# 4gewinnt_01.net
KiCad netlist of a schematic drawn in EAGLE
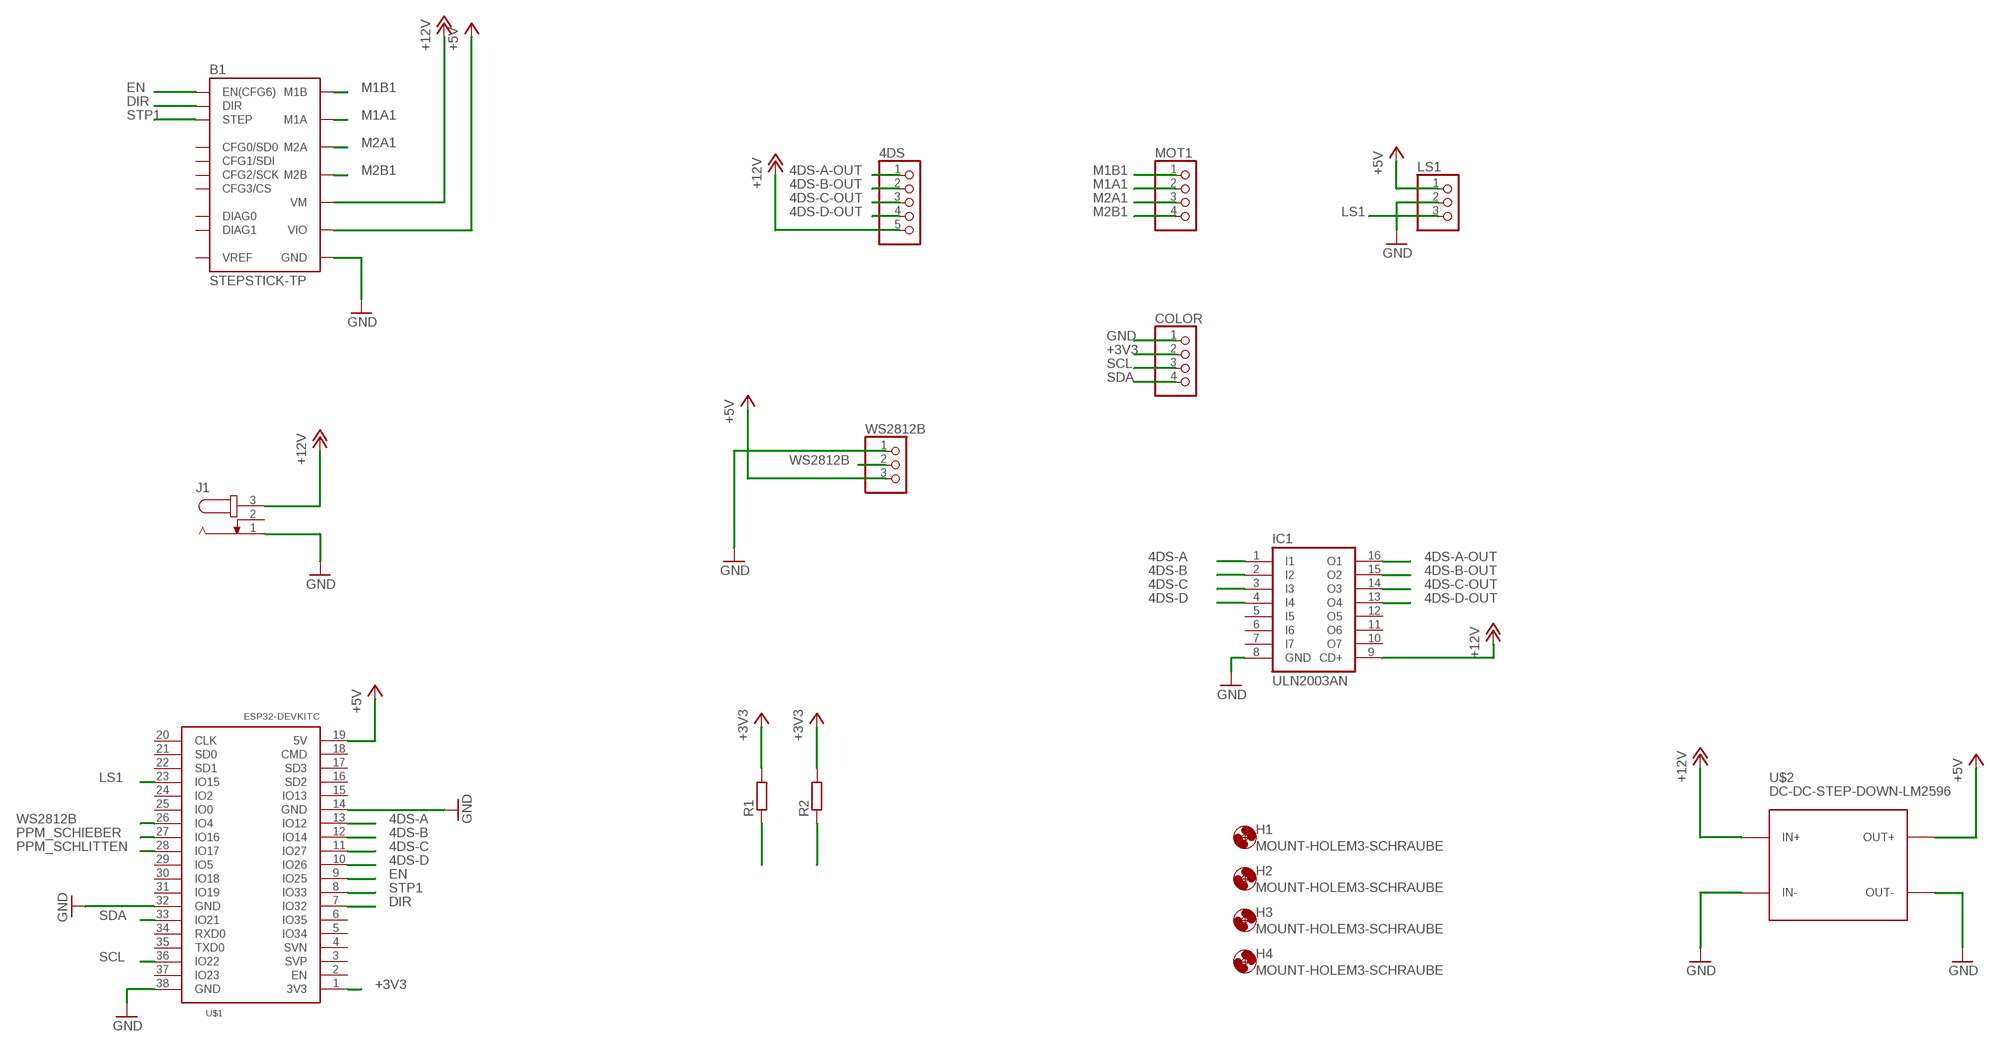
[diagram p0: schematic, sheet 1]

(export (version "E")
  (design (tool "Eeschema 10.0.6"))
  (components
    (comp (ref "4DS")
      (value "PINHD-1X5")
      (footprint "eagle-import:1X05")
      (libsource (lib "eagle-import") (part "PINHD-1X5"))
    )
    (comp (ref "B1")
      (value "STEPSTICK-TP")
      (footprint "eagle-import:STEPSTICK_TP")
      (libsource (lib "eagle-import") (part "STEPSTICK-TP"))
    )
    (comp (ref "COLOR")
      (value "PINHD-1X4")
      (footprint "eagle-import:1X04")
      (libsource (lib "eagle-import") (part "PINHD-1X4"))
    )
    (comp (ref "H1")
      (value "MOUNT-HOLEM3-SCHRAUBE")
      (footprint "eagle-import:M3-SCHRAUBE")
      (libsource (lib "eagle-import") (part "MOUNT-HOLEM3-SCHRAUBE"))
    )
    (comp (ref "H2")
      (value "MOUNT-HOLEM3-SCHRAUBE")
      (footprint "eagle-import:M3-SCHRAUBE")
      (libsource (lib "eagle-import") (part "MOUNT-HOLEM3-SCHRAUBE"))
    )
    (comp (ref "H3")
      (value "MOUNT-HOLEM3-SCHRAUBE")
      (footprint "eagle-import:M3-SCHRAUBE")
      (libsource (lib "eagle-import") (part "MOUNT-HOLEM3-SCHRAUBE"))
    )
    (comp (ref "H4")
      (value "MOUNT-HOLEM3-SCHRAUBE")
      (footprint "eagle-import:M3-SCHRAUBE")
      (libsource (lib "eagle-import") (part "MOUNT-HOLEM3-SCHRAUBE"))
    )
    (comp (ref "IC1")
      (value "ULN2003AN")
      (footprint "eagle-import:DIL16")
      (libsource (lib "eagle-import") (part "ULN2003AN"))
    )
    (comp (ref "J1")
      (value "JACK-PLUG2")
      (footprint "eagle-import:DC5.5-2.5")
      (libsource (lib "eagle-import") (part "JACK-PLUG2"))
    )
    (comp (ref "LS1")
      (value "PINHD-1X3")
      (footprint "eagle-import:1X03")
      (libsource (lib "eagle-import") (part "PINHD-1X3"))
    )
    (comp (ref "MOT1")
      (value "PINHD-1X4")
      (footprint "eagle-import:1X04")
      (libsource (lib "eagle-import") (part "PINHD-1X4"))
    )
    (comp (ref "R1")
      (value "R-EU_0207/15")
      (footprint "eagle-import:0207_15")
      (libsource (lib "eagle-import") (part "R-EU_0207/15"))
    )
    (comp (ref "R2")
      (value "R-EU_0207/15")
      (footprint "eagle-import:0207_15")
      (libsource (lib "eagle-import") (part "R-EU_0207/15"))
    )
    (comp (ref "U$1")
      (value "ESP32DEVKITCAZDELIVERY-ESP32")
      (footprint "eagle-import:AZDELIVERY-ESP32")
      (libsource (lib "eagle-import") (part "ESP32DEVKITCAZDELIVERY-ESP32"))
    )
    (comp (ref "U$2")
      (value "DC-DC-STEP-DOWN-LM2596")
      (footprint "eagle-import:DC-DC-STEP-DOWN-LM2596")
      (libsource (lib "eagle-import") (part "DC-DC-STEP-DOWN-LM2596"))
    )
    (comp (ref "WS2812B")
      (value "PINHD-1X3")
      (footprint "eagle-import:1X03")
      (libsource (lib "eagle-import") (part "PINHD-1X3"))
    )
  )
  (nets
    (net (code "1") (name "+3V3") (class "Default")
      (node (ref "COLOR") (pin "2") (pinfunction "2_2") (pintype "passive"))
      (node (ref "R1") (pin "2") (pinfunction "2_2") (pintype "passive"))
      (node (ref "R2") (pin "2") (pinfunction "2_2") (pintype "passive"))
      (node (ref "U$1") (pin "1") (pinfunction "3V3_1") (pintype "bidirectional"))
    )
    (net (code "2") (name "+5V") (class "Default")
      (node (ref "B1") (pin "VIO") (pinfunction "VIO_VIO") (pintype "power_in"))
      (node (ref "LS1") (pin "1") (pinfunction "1_1") (pintype "passive"))
      (node (ref "U$1") (pin "19") (pinfunction "5V_19") (pintype "bidirectional"))
      (node (ref "U$2") (pin "OUT+") (pinfunction "OUT+_OUT+") (pintype "bidirectional"))
      (node (ref "WS2812B") (pin "3") (pinfunction "3_3") (pintype "passive"))
    )
    (net (code "3") (name "+12V") (class "Default")
      (node (ref "4DS") (pin "5") (pinfunction "5_5") (pintype "passive"))
      (node (ref "B1") (pin "VM") (pinfunction "VM_VM") (pintype "power_in"))
      (node (ref "IC1") (pin "9") (pinfunction "CD+_9") (pintype "passive"))
      (node (ref "J1") (pin "3") (pinfunction "3_3") (pintype "passive"))
      (node (ref "U$2") (pin "IN+") (pinfunction "IN+_IN+") (pintype "bidirectional"))
    )
    (net (code "4") (name "/4DS-A") (class "Default")
      (node (ref "IC1") (pin "1") (pinfunction "I1_1") (pintype "input"))
      (node (ref "U$1") (pin "13") (pinfunction "IO12_13") (pintype "bidirectional"))
    )
    (net (code "5") (name "/4DS-A-OUT") (class "Default")
      (node (ref "4DS") (pin "1") (pinfunction "1_1") (pintype "passive"))
      (node (ref "IC1") (pin "16") (pinfunction "O1_16") (pintype "open_collector"))
    )
    (net (code "6") (name "/4DS-B") (class "Default")
      (node (ref "IC1") (pin "2") (pinfunction "I2_2") (pintype "input"))
      (node (ref "U$1") (pin "12") (pinfunction "IO14_12") (pintype "bidirectional"))
    )
    (net (code "7") (name "/4DS-B-OUT") (class "Default")
      (node (ref "4DS") (pin "2") (pinfunction "2_2") (pintype "passive"))
      (node (ref "IC1") (pin "15") (pinfunction "O2_15") (pintype "open_collector"))
    )
    (net (code "8") (name "/4DS-C") (class "Default")
      (node (ref "IC1") (pin "3") (pinfunction "I3_3") (pintype "input"))
      (node (ref "U$1") (pin "11") (pinfunction "IO27_11") (pintype "bidirectional"))
    )
    (net (code "9") (name "/4DS-C-OUT") (class "Default")
      (node (ref "4DS") (pin "3") (pinfunction "3_3") (pintype "passive"))
      (node (ref "IC1") (pin "14") (pinfunction "O3_14") (pintype "open_collector"))
    )
    (net (code "10") (name "/4DS-D") (class "Default")
      (node (ref "IC1") (pin "4") (pinfunction "I4_4") (pintype "input"))
      (node (ref "U$1") (pin "10") (pinfunction "IO26_10") (pintype "bidirectional"))
    )
    (net (code "11") (name "/4DS-D-OUT") (class "Default")
      (node (ref "4DS") (pin "4") (pinfunction "4_4") (pintype "passive"))
      (node (ref "IC1") (pin "13") (pinfunction "O4_13") (pintype "open_collector"))
    )
    (net (code "12") (name "/DIR") (class "Default")
      (node (ref "B1") (pin "DIR") (pinfunction "DIR_DIR") (pintype "bidirectional"))
      (node (ref "U$1") (pin "7") (pinfunction "IO32_7") (pintype "bidirectional"))
    )
    (net (code "13") (name "/EN") (class "Default")
      (node (ref "B1") (pin "EN") (pinfunction "EN(CFG6)_EN") (pintype "bidirectional"))
      (node (ref "U$1") (pin "9") (pinfunction "IO25_9") (pintype "bidirectional"))
    )
    (net (code "14") (name "/LS1") (class "Default")
      (node (ref "LS1") (pin "3") (pinfunction "3_3") (pintype "passive"))
      (node (ref "U$1") (pin "23") (pinfunction "IO15_23") (pintype "bidirectional"))
    )
    (net (code "15") (name "/M1A1") (class "Default")
      (node (ref "B1") (pin "M1A") (pinfunction "M1A_M1A") (pintype "output"))
      (node (ref "MOT1") (pin "2") (pinfunction "2_2") (pintype "passive"))
    )
    (net (code "16") (name "/M1B1") (class "Default")
      (node (ref "B1") (pin "M1B") (pinfunction "M1B_M1B") (pintype "output"))
      (node (ref "MOT1") (pin "1") (pinfunction "1_1") (pintype "passive"))
    )
    (net (code "17") (name "/M2A1") (class "Default")
      (node (ref "B1") (pin "M2A") (pinfunction "M2A_M2A") (pintype "output"))
      (node (ref "MOT1") (pin "3") (pinfunction "3_3") (pintype "passive"))
    )
    (net (code "18") (name "/M2B1") (class "Default")
      (node (ref "B1") (pin "M2B") (pinfunction "M2B_M2B") (pintype "output"))
      (node (ref "MOT1") (pin "4") (pinfunction "4_4") (pintype "passive"))
    )
    (net (code "19") (name "/PPM_SCHIEBER") (class "Default")
      (node (ref "R1") (pin "1") (pinfunction "1_1") (pintype "passive"))
      (node (ref "U$1") (pin "27") (pinfunction "IO16_27") (pintype "bidirectional"))
    )
    (net (code "20") (name "/PPM_SCHLITTEN") (class "Default")
      (node (ref "R2") (pin "1") (pinfunction "1_1") (pintype "passive"))
      (node (ref "U$1") (pin "28") (pinfunction "IO17_28") (pintype "bidirectional"))
    )
    (net (code "21") (name "/SCL") (class "Default")
      (node (ref "COLOR") (pin "3") (pinfunction "3_3") (pintype "passive"))
      (node (ref "U$1") (pin "36") (pinfunction "IO22_36") (pintype "bidirectional"))
    )
    (net (code "22") (name "/SDA") (class "Default")
      (node (ref "COLOR") (pin "4") (pinfunction "4_4") (pintype "passive"))
      (node (ref "U$1") (pin "33") (pinfunction "IO21_33") (pintype "bidirectional"))
    )
    (net (code "23") (name "/STP1") (class "Default")
      (node (ref "B1") (pin "STEP") (pinfunction "STEP_STEP") (pintype "bidirectional"))
      (node (ref "U$1") (pin "8") (pinfunction "IO33_8") (pintype "bidirectional"))
    )
    (net (code "24") (name "/WS2812B") (class "Default")
      (node (ref "U$1") (pin "26") (pinfunction "IO4_26") (pintype "bidirectional"))
      (node (ref "WS2812B") (pin "2") (pinfunction "2_2") (pintype "passive"))
    )
    (net (code "25") (name "GND") (class "Default")
      (node (ref "B1") (pin "GND@1") (pinfunction "GND_GND@1") (pintype "power_in"))
      (node (ref "B1") (pin "GND@2") (pinfunction "GND_GND@2") (pintype "power_in"))
      (node (ref "COLOR") (pin "1") (pinfunction "1_1") (pintype "passive"))
      (node (ref "IC1") (pin "8") (pinfunction "GND_8") (pintype "power_in"))
      (node (ref "J1") (pin "1") (pinfunction "1_1") (pintype "passive"))
      (node (ref "LS1") (pin "2") (pinfunction "2_2") (pintype "passive"))
      (node (ref "U$1") (pin "14") (pinfunction "GND_14") (pintype "bidirectional"))
      (node (ref "U$1") (pin "32") (pinfunction "GND_32") (pintype "bidirectional"))
      (node (ref "U$1") (pin "38") (pinfunction "GND_38") (pintype "bidirectional"))
      (node (ref "U$2") (pin "IN-") (pinfunction "IN-_IN-") (pintype "bidirectional"))
      (node (ref "U$2") (pin "OUT-") (pinfunction "OUT-_OUT-") (pintype "bidirectional"))
      (node (ref "WS2812B") (pin "1") (pinfunction "1_1") (pintype "passive"))
    )
    (net (code "26") (name "unconnected-(B1-CFG0{slash}SD0-PadNC{slash}CFG0)") (class "Default")
      (node (ref "B1") (pin "NC/CFG0") (pinfunction "CFG0/SD0_NC/CFG0") (pintype "bidirectional"))
    )
    (net (code "27") (name "unconnected-(B1-CFG1{slash}SDI-PadCFG1)") (class "Default")
      (node (ref "B1") (pin "CFG1") (pinfunction "CFG1/SDI_CFG1") (pintype "bidirectional"))
    )
    (net (code "28") (name "unconnected-(B1-CFG2{slash}SCK-PadCFG2)") (class "Default")
      (node (ref "B1") (pin "CFG2") (pinfunction "CFG2/SCK_CFG2") (pintype "bidirectional"))
    )
    (net (code "29") (name "unconnected-(B1-CFG3{slash}CS-PadCFG3)") (class "Default")
      (node (ref "B1") (pin "CFG3") (pinfunction "CFG3/CS_CFG3") (pintype "bidirectional"))
    )
    (net (code "30") (name "unconnected-(B1-PadDIAG0)") (class "Default")
      (node (ref "B1") (pin "DIAG0") (pinfunction "DIAG0_DIAG0") (pintype "bidirectional"))
    )
    (net (code "31") (name "unconnected-(B1-PadDIAG1)") (class "Default")
      (node (ref "B1") (pin "DIAG1") (pinfunction "DIAG1_DIAG1") (pintype "bidirectional"))
    )
    (net (code "32") (name "unconnected-(B1-PadVREF)") (class "Default")
      (node (ref "B1") (pin "VREF") (pinfunction "VREF_VREF") (pintype "passive"))
    )
    (net (code "33") (name "unconnected-(IC1-I5-Pad5)") (class "Default")
      (node (ref "IC1") (pin "5") (pinfunction "I5_5") (pintype "input"))
    )
    (net (code "34") (name "unconnected-(IC1-I6-Pad6)") (class "Default")
      (node (ref "IC1") (pin "6") (pinfunction "I6_6") (pintype "input"))
    )
    (net (code "35") (name "unconnected-(IC1-I7-Pad7)") (class "Default")
      (node (ref "IC1") (pin "7") (pinfunction "I7_7") (pintype "input"))
    )
    (net (code "36") (name "unconnected-(IC1-O5-Pad12)") (class "Default")
      (node (ref "IC1") (pin "12") (pinfunction "O5_12") (pintype "open_collector"))
    )
    (net (code "37") (name "unconnected-(IC1-O6-Pad11)") (class "Default")
      (node (ref "IC1") (pin "11") (pinfunction "O6_11") (pintype "open_collector"))
    )
    (net (code "38") (name "unconnected-(IC1-O7-Pad10)") (class "Default")
      (node (ref "IC1") (pin "10") (pinfunction "O7_10") (pintype "open_collector"))
    )
    (net (code "39") (name "unconnected-(J1-Pad2)") (class "Default")
      (node (ref "J1") (pin "2") (pinfunction "2_2") (pintype "passive"))
    )
    (net (code "40") (name "unconnected-(U$1-CLK-Pad20)") (class "Default")
      (node (ref "U$1") (pin "20") (pinfunction "CLK_20") (pintype "bidirectional"))
    )
    (net (code "41") (name "unconnected-(U$1-CMD-Pad18)") (class "Default")
      (node (ref "U$1") (pin "18") (pinfunction "CMD_18") (pintype "bidirectional"))
    )
    (net (code "42") (name "unconnected-(U$1-EN-Pad2)") (class "Default")
      (node (ref "U$1") (pin "2") (pinfunction "EN_2") (pintype "bidirectional"))
    )
    (net (code "43") (name "unconnected-(U$1-IO0-Pad25)") (class "Default")
      (node (ref "U$1") (pin "25") (pinfunction "IO0_25") (pintype "bidirectional"))
    )
    (net (code "44") (name "unconnected-(U$1-IO2-Pad24)") (class "Default")
      (node (ref "U$1") (pin "24") (pinfunction "IO2_24") (pintype "bidirectional"))
    )
    (net (code "45") (name "unconnected-(U$1-IO5-Pad29)") (class "Default")
      (node (ref "U$1") (pin "29") (pinfunction "IO5_29") (pintype "bidirectional"))
    )
    (net (code "46") (name "unconnected-(U$1-IO13-Pad15)") (class "Default")
      (node (ref "U$1") (pin "15") (pinfunction "IO13_15") (pintype "bidirectional"))
    )
    (net (code "47") (name "unconnected-(U$1-IO18-Pad30)") (class "Default")
      (node (ref "U$1") (pin "30") (pinfunction "IO18_30") (pintype "bidirectional"))
    )
    (net (code "48") (name "unconnected-(U$1-IO19-Pad31)") (class "Default")
      (node (ref "U$1") (pin "31") (pinfunction "IO19_31") (pintype "bidirectional"))
    )
    (net (code "49") (name "unconnected-(U$1-IO23-Pad37)") (class "Default")
      (node (ref "U$1") (pin "37") (pinfunction "IO23_37") (pintype "bidirectional"))
    )
    (net (code "50") (name "unconnected-(U$1-IO34-Pad5)") (class "Default")
      (node (ref "U$1") (pin "5") (pinfunction "IO34_5") (pintype "bidirectional"))
    )
    (net (code "51") (name "unconnected-(U$1-IO35-Pad6)") (class "Default")
      (node (ref "U$1") (pin "6") (pinfunction "IO35_6") (pintype "bidirectional"))
    )
    (net (code "52") (name "unconnected-(U$1-RXD0-Pad34)") (class "Default")
      (node (ref "U$1") (pin "34") (pinfunction "RXD0_34") (pintype "bidirectional"))
    )
    (net (code "53") (name "unconnected-(U$1-SD0-Pad21)") (class "Default")
      (node (ref "U$1") (pin "21") (pinfunction "SD0_21") (pintype "bidirectional"))
    )
    (net (code "54") (name "unconnected-(U$1-SD1-Pad22)") (class "Default")
      (node (ref "U$1") (pin "22") (pinfunction "SD1_22") (pintype "bidirectional"))
    )
    (net (code "55") (name "unconnected-(U$1-SD2-Pad16)") (class "Default")
      (node (ref "U$1") (pin "16") (pinfunction "SD2_16") (pintype "bidirectional"))
    )
    (net (code "56") (name "unconnected-(U$1-SD3-Pad17)") (class "Default")
      (node (ref "U$1") (pin "17") (pinfunction "SD3_17") (pintype "bidirectional"))
    )
    (net (code "57") (name "unconnected-(U$1-SVN-Pad4)") (class "Default")
      (node (ref "U$1") (pin "4") (pinfunction "SVN_4") (pintype "bidirectional"))
    )
    (net (code "58") (name "unconnected-(U$1-SVP-Pad3)") (class "Default")
      (node (ref "U$1") (pin "3") (pinfunction "SVP_3") (pintype "bidirectional"))
    )
    (net (code "59") (name "unconnected-(U$1-TXD0-Pad35)") (class "Default")
      (node (ref "U$1") (pin "35") (pinfunction "TXD0_35") (pintype "bidirectional"))
    )
  )
)
